# Seq.net
KiCad netlist of a schematic drawn in Altium Designer
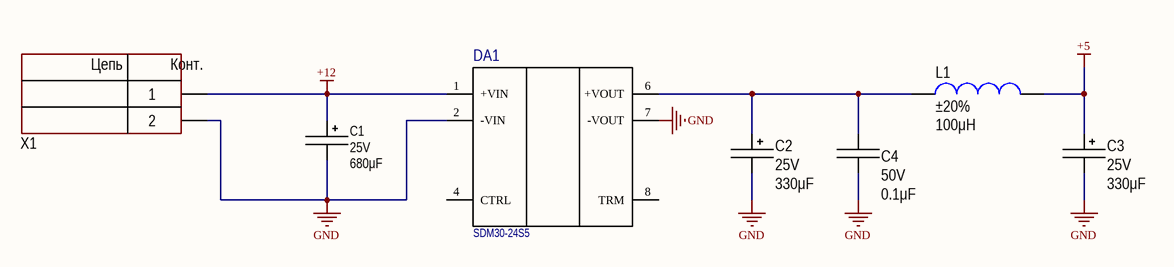
[diagram p0: Seq.SchDoc]

(export (version "E")
  (design (tool "Eeschema 10.0.6"))
  (components
    (comp (ref "C1")
      (value "680μF")
      (footprint "standard-case:CAP: D10C5H16")
      (fields
        (field (name "MANUFACTURER") "Wurth")
        (field (name "PARTNUMBER") "860080475013")
        (field (name "VALUEMANUFACTURERPARTNUMBER") "Aluminium capacitor, 680μF, 25V, ±20%, 54mOhm, 14x10x5 mm, -55...+105°C")
        (field (name "VOLTAGE") "25V")
      )
      (libsource (lib "capacitor") (part "Aluminium"))
    )
    (comp (ref "C2")
      (value "330μF")
      (footprint "standard-case:CAP: D6.3C2.5H11")
      (fields
        (field (name "MANUFACTURER") "Wurth")
        (field (name "PARTNUMBER") "860080475013")
        (field (name "VALUEMANUFACTURERPARTNUMBER") "Aluminium capacitor, 330μF, 25V, ±20%, 54mOhm, 14x10x5 mm, -55...+105°C")
        (field (name "VOLTAGE") "25V")
      )
      (libsource (lib "capacitor") (part "Aluminium"))
    )
    (comp (ref "C3")
      (value "330μF")
      (footprint "standard-case:CAP: D6.3C2.5H11")
      (fields
        (field (name "MANUFACTURER") "Wurth")
        (field (name "PARTNUMBER") "860080475013")
        (field (name "VALUEMANUFACTURERPARTNUMBER") "Aluminium capacitor, 330μF, 25V, ±20%, 54mOhm, 14x10x5 mm, -55...+105°C")
        (field (name "VOLTAGE") "25V")
      )
      (libsource (lib "capacitor") (part "Aluminium"))
    )
    (comp (ref "C4")
      (value "0.1μF")
      (footprint "standard-case:CAP: 1206")
      (fields
        (field (name "MANUFACTURER") "Yageo")
        (field (name "PARTNUMBER") "CC1206KRX7R9BB104")
        (field (name "VALUEMANUFACTURERPARTNUMBER") "Ceramic capacitor, 0.1μF, X7R, ±10%, 50V, 1206, -55...+125°C")
        (field (name "VOLTAGE") "50V")
      )
      (libsource (lib "capacitor") (part "Ceramic_1206"))
    )
    (comp (ref "DA1")
      (value "SDM30-24S5")
      (footprint "SDM3024S5")
      (description "Power Supply")
      (libsource (lib "SDM30-24S5") (part "SDM30-24S5"))
    )
    (comp (ref "L1")
      (value "100μH")
      (footprint "SRR1208-101YL")
      (fields
        (field (name "MANUFACTURER") "Bourns")
        (field (name "PARTNUMBER") "SDR0403-4R7ML")
        (field (name "VALUEMANUFACTURERPARTNUMBER") "Fixed inductor, 100μH, ±20%, SDR0403, 1.7A, -40...+125°C")
        (field (name "TOLERANCE") "±20%")
      )
      (libsource (lib "SRR1208-101YL") (part "Inductor_SDR0403"))
    )
    (comp (ref "X1")
      (value "~")
      (footprint "2EDGR-5.08-02P")
      (fields
        (field (name "MANUFACTURER") "Connfly")
        (field (name "VALUEMANUFACTURERPARTNUMBER") "Connector, 6pin, 2.54mm, 500VAC, 3A")
        (field (name "PARTNUMBER") "PBS-6")
      )
      (libsource (lib "K3NG_SCH_Libs") (part "2EDGR-5.08-02P"))
    )
  )
  (nets
    (net (code "1") (name "+5") (class "Default")
      (node (ref "C3") (pin "1") (pinfunction "1_1") (pintype "passive"))
      (node (ref "L1") (pin "1") (pinfunction "1_1") (pintype "passive"))
    )
    (net (code "2") (name "+12") (class "Default")
      (node (ref "C1") (pin "1") (pinfunction "1_1") (pintype "passive"))
      (node (ref "DA1") (pin "1") (pinfunction "+VIN_1") (pintype "passive"))
      (node (ref "X1") (pin "1") (pinfunction "1_1") (pintype "passive"))
    )
    (net (code "3") (name "GND") (class "Default")
      (node (ref "C1") (pin "2") (pinfunction "2_2") (pintype "passive"))
      (node (ref "C2") (pin "2") (pinfunction "2_2") (pintype "passive"))
      (node (ref "C3") (pin "2") (pinfunction "2_2") (pintype "passive"))
      (node (ref "C4") (pin "1") (pinfunction "1_1") (pintype "passive"))
      (node (ref "DA1") (pin "2") (pinfunction "-VIN_2") (pintype "passive"))
      (node (ref "DA1") (pin "7") (pinfunction "-VOUT_7") (pintype "passive"))
      (node (ref "X1") (pin "2") (pinfunction "2_2") (pintype "passive"))
    )
    (net (code "4") (name "Net-(DA1-+VOUT)") (class "Default")
      (node (ref "C2") (pin "1") (pinfunction "1_1") (pintype "passive"))
      (node (ref "C4") (pin "2") (pinfunction "2_2") (pintype "passive"))
      (node (ref "DA1") (pin "6") (pinfunction "+VOUT_6") (pintype "passive"))
      (node (ref "L1") (pin "2") (pinfunction "2_2") (pintype "passive"))
    )
    (net (code "5") (name "unconnected-(DA1-CTRL-Pad4)") (class "Default")
      (node (ref "DA1") (pin "4") (pinfunction "CTRL_4") (pintype "passive"))
    )
    (net (code "6") (name "unconnected-(DA1-TRM-Pad8)") (class "Default")
      (node (ref "DA1") (pin "8") (pinfunction "TRM_8") (pintype "passive"))
    )
  )
)
